# Power.net
KiCad netlist of a schematic drawn in Altium Designer
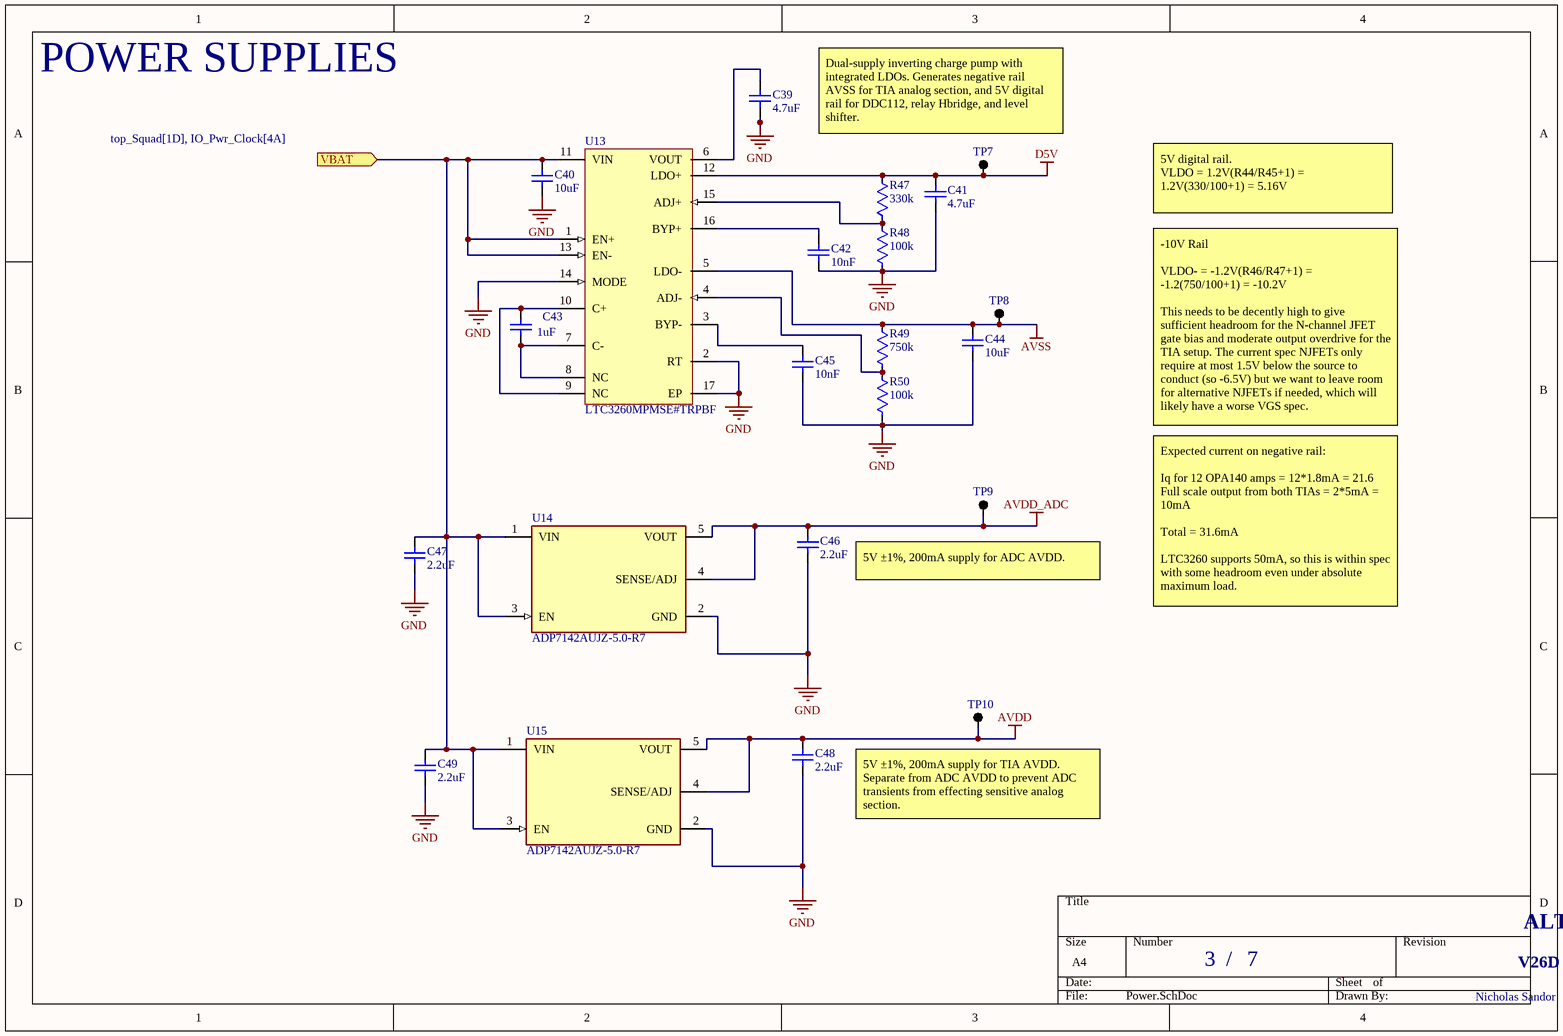
[diagram p0: Power.SchDoc]

(export (version "E")
  (design (tool "Eeschema 10.0.6"))
  (components
    (comp (ref "C39")
      (value "4.7uF")
      (footprint "CAP 0805 IPC MID DENSITY")
      (description "Murata GRM21BR61E106KA73L - Cap Ceramic 10uF 10% 25V X5R 0805")
      (fields (field (name "MF") "Murata") (field (name "MP") "GRM21BR61E106KA73L"))
      (libsource (lib "ALTAIR_PD_Capacitors") (part "CAP"))
    )
    (comp (ref "C40")
      (value "10uF")
      (footprint "CAP 0805 IPC MID DENSITY")
      (description "Murata GRM21BR61E106KA73L - Cap Ceramic 10uF 10% 25V X5R 0805")
      (fields (field (name "MF") "Murata") (field (name "MP") "GRM21BR61E106KA73L"))
      (libsource (lib "ALTAIR_PD_Capacitors") (part "CAP"))
    )
    (comp (ref "C41")
      (value "4.7uF")
      (footprint "CAP 0805 IPC MID DENSITY")
      (description "Murata GRM21BR61E106KA73L - Cap Ceramic 10uF 10% 25V X5R 0805")
      (fields (field (name "MF") "Murata") (field (name "MP") "GRM21BR61E106KA73L"))
      (libsource (lib "ALTAIR_PD_Capacitors") (part "CAP"))
    )
    (comp (ref "C42")
      (value "10nF")
      (footprint "CAP 0603 IPC MID DENSITY MURATA")
      (description "Murata GRM21BR61E106KA73L - Cap Ceramic 10uF 10% 25V X5R 0805")
      (fields (field (name "MF") "Murata") (field (name "MP") "GRM21BR61E106KA73L"))
      (libsource (lib "ALTAIR_PD_Capacitors") (part "CAP"))
    )
    (comp (ref "C43")
      (value "1uF")
      (footprint "CAP 0805 IPC MID DENSITY")
      (description "Murata GRM21BR61E106KA73L - Cap Ceramic 10uF 10% 25V X5R 0805")
      (fields (field (name "MF") "Murata") (field (name "MP") "GRM21BR61E106KA73L"))
      (libsource (lib "ALTAIR_PD_Capacitors") (part "CAP"))
    )
    (comp (ref "C44")
      (value "10uF")
      (footprint "CAP 0805 IPC MID DENSITY")
      (description "Murata GRM21BR61E106KA73L - Cap Ceramic 10uF 10% 25V X5R 0805")
      (fields (field (name "MF") "Murata") (field (name "MP") "GRM21BR61E106KA73L"))
      (libsource (lib "ALTAIR_PD_Capacitors") (part "CAP"))
    )
    (comp (ref "C45")
      (value "10nF")
      (footprint "CAP 0603 IPC MID DENSITY MURATA")
      (description "Murata GRM21BR61E106KA73L - Cap Ceramic 10uF 10% 25V X5R 0805")
      (fields (field (name "MF") "Murata") (field (name "MP") "GRM21BR61E106KA73L"))
      (libsource (lib "ALTAIR_PD_Capacitors") (part "CAP"))
    )
    (comp (ref "C46")
      (value "2.2uF")
      (footprint "CAP 1206 UNKNOWN")
      (description "CL31B225KBHNNNE CAP CER 2.2UF 50V X7R 1206")
      (fields (field (name "MF") "Samsung Electro-Mechanics") (field (name "MP") "CL31B225KBHNNNE"))
      (libsource (lib "ALTAIR_PD_Capacitors") (part "CAP"))
    )
    (comp (ref "C47")
      (value "2.2uF")
      (footprint "CAP 1206 UNKNOWN")
      (description "CL31B225KBHNNNE CAP CER 2.2UF 50V X7R 1206")
      (fields (field (name "MF") "Samsung Electro-Mechanics") (field (name "MP") "CL31B225KBHNNNE"))
      (libsource (lib "ALTAIR_PD_Capacitors") (part "CAP"))
    )
    (comp (ref "C48")
      (value "2.2uF")
      (footprint "CAP 1206 UNKNOWN")
      (description "CL31B225KBHNNNE CAP CER 2.2UF 50V X7R 1206")
      (fields (field (name "MF") "Samsung Electro-Mechanics") (field (name "MP") "CL31B225KBHNNNE"))
      (libsource (lib "ALTAIR_PD_Capacitors") (part "CAP"))
    )
    (comp (ref "C49")
      (value "2.2uF")
      (footprint "CAP 1206 UNKNOWN")
      (description "CL31B225KBHNNNE CAP CER 2.2UF 50V X7R 1206")
      (fields (field (name "MF") "Samsung Electro-Mechanics") (field (name "MP") "CL31B225KBHNNNE"))
      (libsource (lib "ALTAIR_PD_Capacitors") (part "CAP"))
    )
    (comp (ref "R47")
      (value "330k")
      (footprint "RES 0603 IPC MID DENSITY")
      (description "Panasonic ERJ-3EKF2001V Res Thick Film 0603 2K Ohm 1% 1/10W ±100ppm/°C")
      (fields (field (name "MF") "Panasonic Electronic Components") (field (name "MP") "ERJ-3EKF2001V"))
      (libsource (lib "ALTAIR_PD_Resistors") (part "RES"))
    )
    (comp (ref "R48")
      (value "100k")
      (footprint "RES 0603 IPC MID DENSITY")
      (fields (field (name "MF") "UNI-ROYAL(Uniroyal Elec)") (field (name "MP") "0603WAF1003T5E"))
      (libsource (lib "ALTAIR_PD_Resistors") (part "RES"))
    )
    (comp (ref "R49")
      (value "750k")
      (footprint "RES 0603 IPC MID DENSITY")
      (description "Panasonic ERJ-3EKF2001V Res Thick Film 0603 2K Ohm 1% 1/10W ±100ppm/°C")
      (fields (field (name "MF") "Panasonic Electronic Components") (field (name "MP") "ERJ-3EKF2001V"))
      (libsource (lib "ALTAIR_PD_Resistors") (part "RES"))
    )
    (comp (ref "R50")
      (value "100k")
      (footprint "RES 0603 IPC MID DENSITY")
      (fields (field (name "MF") "UNI-ROYAL(Uniroyal Elec)") (field (name "MP") "0603WAF1003T5E"))
      (libsource (lib "ALTAIR_PD_Resistors") (part "RES"))
    )
    (comp (ref "TP7")
      (value "Testpoint")
      (footprint "TESTPOINT THT")
      (libsource (lib "ALTAIR_PD_Testpoint") (part "Testpoint"))
    )
    (comp (ref "TP8")
      (value "Testpoint")
      (footprint "TESTPOINT THT")
      (libsource (lib "ALTAIR_PD_Testpoint") (part "Testpoint"))
    )
    (comp (ref "TP9")
      (value "Testpoint")
      (footprint "TESTPOINT THT")
      (libsource (lib "ALTAIR_PD_Testpoint") (part "Testpoint"))
    )
    (comp (ref "TP10")
      (value "Testpoint")
      (footprint "TESTPOINT THT")
      (libsource (lib "ALTAIR_PD_Testpoint") (part "Testpoint"))
    )
    (comp (ref "U13")
      (value "LTC3260MPMSE#TRPBF")
      (footprint "LT-MSE-16-EDP_L")
      (fields (field (name "MANUFACTURER") "Linear Technology"))
      (libsource (lib "ALTAIR_PD_Converters") (part "CMP-0475-00262-1"))
    )
    (comp (ref "U14")
      (value "ADP7142AUJZ-5.0-R7")
      (footprint "SOT23-5 HIGH DENSITY AD")
      (description "1.2-40V 200mA Low Noise CMOS LDO Adjustable Linear Regulator TSOT23")
      (fields
        (field (name "OCTOPART") "https://octopart.com/adp7142aujz-r7-analog+devices-38928114")
        (field (name "MF") "Analog Devices")
      )
      (libsource (lib "ALTAIR_PD_Regulators") (part "ADP7142AUJZ-R7"))
    )
    (comp (ref "U15")
      (value "ADP7142AUJZ-5.0-R7")
      (footprint "SOT23-5 HIGH DENSITY AD")
      (description "1.2-40V 200mA Low Noise CMOS LDO Adjustable Linear Regulator TSOT23")
      (fields
        (field (name "OCTOPART") "https://octopart.com/adp7142aujz-r7-analog+devices-38928114")
        (field (name "MF") "Analog Devices")
      )
      (libsource (lib "ALTAIR_PD_Regulators") (part "ADP7142AUJZ-R7"))
    )
  )
  (nets
    (net (code "1") (name "/VBAT") (class "Default")
      (node (ref "C40") (pin "2") (pinfunction "2_2") (pintype "passive"))
      (node (ref "C47") (pin "1") (pinfunction "1_1") (pintype "passive"))
      (node (ref "C49") (pin "1") (pinfunction "1_1") (pintype "passive"))
      (node (ref "U13") (pin "1") (pinfunction "EN+_1") (pintype "input"))
      (node (ref "U13") (pin "11") (pinfunction "VIN_11") (pintype "power_in"))
      (node (ref "U13") (pin "13") (pinfunction "EN-_13") (pintype "input"))
      (node (ref "U14") (pin "1") (pinfunction "VIN_1") (pintype "power_in"))
      (node (ref "U14") (pin "3") (pinfunction "EN_3") (pintype "input"))
      (node (ref "U15") (pin "1") (pinfunction "VIN_1") (pintype "power_in"))
      (node (ref "U15") (pin "3") (pinfunction "EN_3") (pintype "input"))
    )
    (net (code "2") (name "AVDD") (class "Default")
      (node (ref "C48") (pin "1") (pinfunction "1_1") (pintype "passive"))
      (node (ref "TP10") (pin "1") (pinfunction "1_1") (pintype "passive"))
      (node (ref "U15") (pin "4") (pinfunction "SENSE/ADJ_4") (pintype "passive"))
      (node (ref "U15") (pin "5") (pinfunction "VOUT_5") (pintype "passive"))
    )
    (net (code "3") (name "AVDD_ADC") (class "Default")
      (node (ref "C46") (pin "1") (pinfunction "1_1") (pintype "passive"))
      (node (ref "TP9") (pin "1") (pinfunction "1_1") (pintype "passive"))
      (node (ref "U14") (pin "4") (pinfunction "SENSE/ADJ_4") (pintype "passive"))
      (node (ref "U14") (pin "5") (pinfunction "VOUT_5") (pintype "passive"))
    )
    (net (code "4") (name "AVSS") (class "Default")
      (node (ref "C44") (pin "2") (pinfunction "2_2") (pintype "passive"))
      (node (ref "R49") (pin "2") (pinfunction "2_2") (pintype "passive"))
      (node (ref "TP8") (pin "1") (pinfunction "1_1") (pintype "passive"))
      (node (ref "U13") (pin "5") (pinfunction "LDO-_5") (pintype "power_in"))
    )
    (net (code "5") (name "D5V") (class "Default")
      (node (ref "C41") (pin "2") (pinfunction "2_2") (pintype "passive"))
      (node (ref "R47") (pin "2") (pinfunction "2_2") (pintype "passive"))
      (node (ref "TP7") (pin "1") (pinfunction "1_1") (pintype "passive"))
      (node (ref "U13") (pin "12") (pinfunction "LDO+_12") (pintype "power_in"))
    )
    (net (code "6") (name "GND") (class "Default")
      (node (ref "C39") (pin "1") (pinfunction "1_1") (pintype "passive"))
      (node (ref "C40") (pin "1") (pinfunction "1_1") (pintype "passive"))
      (node (ref "C41") (pin "1") (pinfunction "1_1") (pintype "passive"))
      (node (ref "C42") (pin "1") (pinfunction "1_1") (pintype "passive"))
      (node (ref "C44") (pin "1") (pinfunction "1_1") (pintype "passive"))
      (node (ref "C45") (pin "1") (pinfunction "1_1") (pintype "passive"))
      (node (ref "C46") (pin "2") (pinfunction "2_2") (pintype "passive"))
      (node (ref "C47") (pin "2") (pinfunction "2_2") (pintype "passive"))
      (node (ref "C48") (pin "2") (pinfunction "2_2") (pintype "passive"))
      (node (ref "C49") (pin "2") (pinfunction "2_2") (pintype "passive"))
      (node (ref "R48") (pin "1") (pinfunction "1_1") (pintype "passive"))
      (node (ref "R50") (pin "1") (pinfunction "1_1") (pintype "passive"))
      (node (ref "U13") (pin "14") (pinfunction "MODE_14") (pintype "input"))
      (node (ref "U13") (pin "17") (pinfunction "EP_17") (pintype "power_in"))
      (node (ref "U13") (pin "2") (pinfunction "RT_2") (pintype "passive"))
      (node (ref "U14") (pin "2") (pinfunction "GND_2") (pintype "power_in"))
      (node (ref "U15") (pin "2") (pinfunction "GND_2") (pintype "power_in"))
    )
    (net (code "7") (name "Net-(U13-ADJ+)") (class "Default")
      (node (ref "R47") (pin "1") (pinfunction "1_1") (pintype "passive"))
      (node (ref "R48") (pin "2") (pinfunction "2_2") (pintype "passive"))
      (node (ref "U13") (pin "15") (pinfunction "ADJ+_15") (pintype "input"))
    )
    (net (code "8") (name "Net-(U13-ADJ-)") (class "Default")
      (node (ref "R49") (pin "1") (pinfunction "1_1") (pintype "passive"))
      (node (ref "R50") (pin "2") (pinfunction "2_2") (pintype "passive"))
      (node (ref "U13") (pin "4") (pinfunction "ADJ-_4") (pintype "input"))
    )
    (net (code "9") (name "Net-(U13-BYP+)") (class "Default")
      (node (ref "C42") (pin "2") (pinfunction "2_2") (pintype "passive"))
      (node (ref "U13") (pin "16") (pinfunction "BYP+_16") (pintype "passive"))
    )
    (net (code "10") (name "Net-(U13-BYP-)") (class "Default")
      (node (ref "C45") (pin "2") (pinfunction "2_2") (pintype "passive"))
      (node (ref "U13") (pin "3") (pinfunction "BYP-_3") (pintype "passive"))
    )
    (net (code "11") (name "Net-(U13-C+)") (class "Default")
      (node (ref "C43") (pin "2") (pinfunction "2_2") (pintype "passive"))
      (node (ref "U13") (pin "10") (pinfunction "C+_10") (pintype "passive"))
      (node (ref "U13") (pin "9") (pinfunction "NC_9") (pintype "passive"))
    )
    (net (code "12") (name "Net-(U13-C-)") (class "Default")
      (node (ref "C43") (pin "1") (pinfunction "1_1") (pintype "passive"))
      (node (ref "U13") (pin "7") (pinfunction "C-_7") (pintype "passive"))
      (node (ref "U13") (pin "8") (pinfunction "NC_8") (pintype "passive"))
    )
    (net (code "13") (name "Net-(U13-VOUT)") (class "Default")
      (node (ref "C39") (pin "2") (pinfunction "2_2") (pintype "passive"))
      (node (ref "U13") (pin "6") (pinfunction "VOUT_6") (pintype "power_in"))
    )
  )
)
